# USB_C_Connectors.net
KiCad netlist of a schematic drawn in Altium Designer
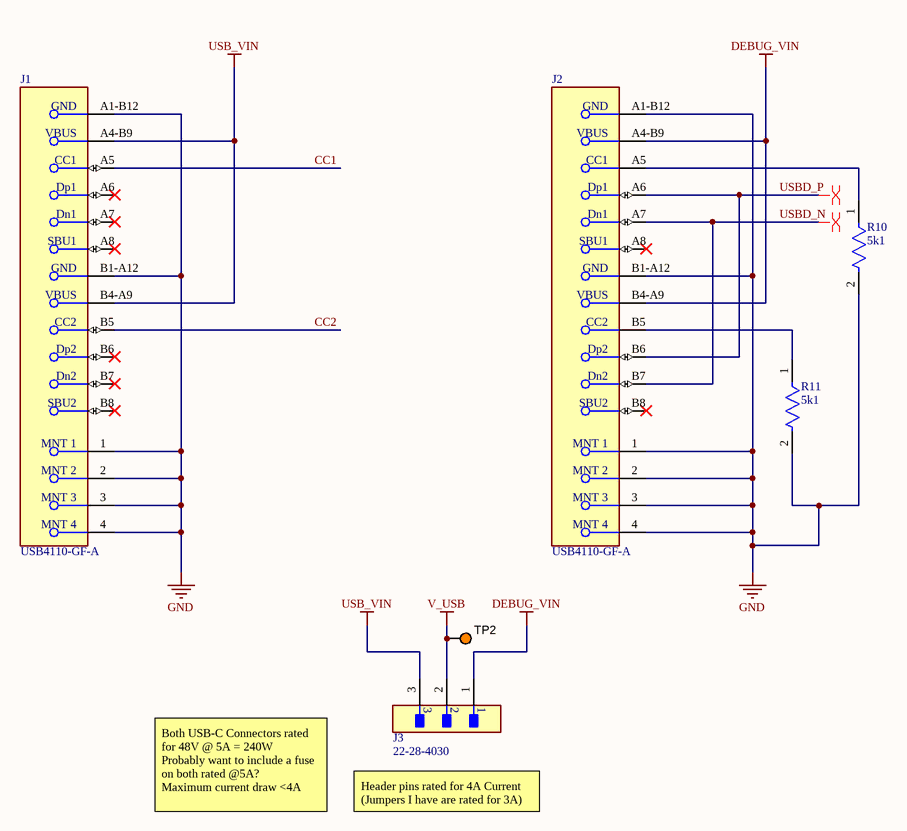
[diagram p0: USB_C_Connectors.SchDoc]

(export (version "E")
  (design (tool "Eeschema 10.0.6"))
  (components
    (comp (ref "J1")
      (value "USB4110-GF-A")
      (footprint "FP-USB4110-GF-A-MFG")
      (description "CONN USB 2.0 TYPE-C R/A SMT")
      (fields
        (field (name "OCTOPART") "https://octopart.com/usb4110-gf-a-gct-103941985")
        (field (name "MANUFACTURER") "GCT")
      )
      (libsource (lib "Altium Content Vault") (part "e23f2b38bb3c3f98e683ebab9ede730"))
    )
    (comp (ref "J2")
      (value "USB4110-GF-A")
      (footprint "FP-USB4110-GF-A-MFG")
      (description "CONN USB 2.0 TYPE-C R/A SMT")
      (fields
        (field (name "OCTOPART") "https://octopart.com/usb4110-gf-a-gct-103941985")
        (field (name "MANUFACTURER") "GCT")
      )
      (libsource (lib "Altium Content Vault") (part "e23f2b38bb3c3f98e683ebab9ede730"))
    )
    (comp (ref "J3")
      (value "22-28-4030")
      (footprint "FP-22-28-4030-MFG")
      (description "CONN HEADER VERT 3POS 2.54MM")
      (fields
        (field (name "OCTOPART") "https://octopart.com/0022284030-molex-10476094")
        (field (name "MANUFACTURER") "Molex")
      )
      (libsource (lib "Altium Content Vault") (part "0d3f023dd272f625e17a2be33dea85f"))
    )
    (comp (ref "R10")
      (value "5k1")
      (footprint "FP-CRCW0603-C-MFG")
      (description "RES 5.1K OHM 5% 1/10W 0603")
      (fields (field (name "TOLERANCE") "5%"))
      (libsource (lib "Altium Content Vault") (part "1029c3af85768c4190bb7ad29bc67b5"))
    )
    (comp (ref "R11")
      (value "5k1")
      (footprint "FP-CRCW0603-C-MFG")
      (description "RES 5.1K OHM 5% 1/10W 0603")
      (fields (field (name "TOLERANCE") "5%"))
      (libsource (lib "Altium Content Vault") (part "1029c3af85768c4190bb7ad29bc67b5"))
    )
    (comp (ref "TP2")
      (value "5003")
      (footprint "KSTN-5003")
      (description "Test Point, Orange, 1-Pin THD, RoHS")
      (libsource (lib "Altium Content Vault") (part "TESTPOINT_ORANGE"))
    )
  )
  (nets
    (net (code "1") (name "/CC1") (class "Default")
      (node (ref "J1") (pin "A5") (pinfunction "CC1_A5") (pintype "bidirectional"))
    )
    (net (code "2") (name "/CC2") (class "Default")
      (node (ref "J1") (pin "B5") (pinfunction "CC2_B5") (pintype "bidirectional"))
    )
    (net (code "3") (name "/USBD_N") (class "Default")
      (node (ref "J2") (pin "A7") (pinfunction "Dn1_A7") (pintype "bidirectional"))
      (node (ref "J2") (pin "B7") (pinfunction "Dn2_B7") (pintype "bidirectional"))
    )
    (net (code "4") (name "/USBD_P") (class "Default")
      (node (ref "J2") (pin "A6") (pinfunction "Dp1_A6") (pintype "bidirectional"))
      (node (ref "J2") (pin "B6") (pinfunction "Dp2_B6") (pintype "bidirectional"))
    )
    (net (code "5") (name "DEBUG_VIN") (class "Default")
      (node (ref "J2") (pin "A4-B9") (pinfunction "VBUS_A4-B9") (pintype "power_in"))
      (node (ref "J2") (pin "B4-A9") (pinfunction "VBUS_B4-A9") (pintype "power_in"))
      (node (ref "J3") (pin "1") (pinfunction "1_1") (pintype "passive"))
    )
    (net (code "6") (name "GND") (class "Default")
      (node (ref "J1") (pin "1") (pinfunction "MNT_1_1") (pintype "passive"))
      (node (ref "J1") (pin "2") (pinfunction "MNT_2_2") (pintype "passive"))
      (node (ref "J1") (pin "3") (pinfunction "MNT_3_3") (pintype "passive"))
      (node (ref "J1") (pin "4") (pinfunction "MNT_4_4") (pintype "passive"))
      (node (ref "J1") (pin "A1-B12") (pinfunction "GND_A1-B12") (pintype "passive"))
      (node (ref "J1") (pin "B1-A12") (pinfunction "GND_B1-A12") (pintype "passive"))
      (node (ref "J2") (pin "1") (pinfunction "MNT_1_1") (pintype "passive"))
      (node (ref "J2") (pin "2") (pinfunction "MNT_2_2") (pintype "passive"))
      (node (ref "J2") (pin "3") (pinfunction "MNT_3_3") (pintype "passive"))
      (node (ref "J2") (pin "4") (pinfunction "MNT_4_4") (pintype "passive"))
      (node (ref "J2") (pin "A1-B12") (pinfunction "GND_A1-B12") (pintype "passive"))
      (node (ref "J2") (pin "B1-A12") (pinfunction "GND_B1-A12") (pintype "passive"))
      (node (ref "R10") (pin "2") (pinfunction "2_2") (pintype "passive"))
      (node (ref "R11") (pin "2") (pinfunction "2_2") (pintype "passive"))
    )
    (net (code "7") (name "Net-(J2-CC1)") (class "Default")
      (node (ref "J2") (pin "A5") (pinfunction "CC1_A5") (pintype "bidirectional"))
      (node (ref "R10") (pin "1") (pinfunction "1_1") (pintype "passive"))
    )
    (net (code "8") (name "Net-(J2-CC2)") (class "Default")
      (node (ref "J2") (pin "B5") (pinfunction "CC2_B5") (pintype "bidirectional"))
      (node (ref "R11") (pin "1") (pinfunction "1_1") (pintype "passive"))
    )
    (net (code "9") (name "USB_VIN") (class "Default")
      (node (ref "J1") (pin "A4-B9") (pinfunction "VBUS_A4-B9") (pintype "power_in"))
      (node (ref "J1") (pin "B4-A9") (pinfunction "VBUS_B4-A9") (pintype "power_in"))
      (node (ref "J3") (pin "3") (pinfunction "3_3") (pintype "passive"))
    )
    (net (code "10") (name "V_USB") (class "Default")
      (node (ref "J3") (pin "2") (pinfunction "2_2") (pintype "passive"))
      (node (ref "TP2") (pin "1") (pinfunction "1_1") (pintype "passive"))
    )
    (net (code "11") (name "unconnected-(J1-Dn1-PadA7)") (class "Default")
      (node (ref "J1") (pin "A7") (pinfunction "Dn1_A7") (pintype "bidirectional+no_connect"))
    )
    (net (code "12") (name "unconnected-(J1-Dn2-PadB7)") (class "Default")
      (node (ref "J1") (pin "B7") (pinfunction "Dn2_B7") (pintype "bidirectional+no_connect"))
    )
    (net (code "13") (name "unconnected-(J1-Dp1-PadA6)") (class "Default")
      (node (ref "J1") (pin "A6") (pinfunction "Dp1_A6") (pintype "bidirectional+no_connect"))
    )
    (net (code "14") (name "unconnected-(J1-Dp2-PadB6)") (class "Default")
      (node (ref "J1") (pin "B6") (pinfunction "Dp2_B6") (pintype "bidirectional+no_connect"))
    )
    (net (code "15") (name "unconnected-(J1-SBU1-PadA8)") (class "Default")
      (node (ref "J1") (pin "A8") (pinfunction "SBU1_A8") (pintype "bidirectional+no_connect"))
    )
    (net (code "16") (name "unconnected-(J1-SBU2-PadB8)") (class "Default")
      (node (ref "J1") (pin "B8") (pinfunction "SBU2_B8") (pintype "bidirectional+no_connect"))
    )
    (net (code "17") (name "unconnected-(J2-SBU1-PadA8)") (class "Default")
      (node (ref "J2") (pin "A8") (pinfunction "SBU1_A8") (pintype "bidirectional+no_connect"))
    )
    (net (code "18") (name "unconnected-(J2-SBU2-PadB8)") (class "Default")
      (node (ref "J2") (pin "B8") (pinfunction "SBU2_B8") (pintype "bidirectional+no_connect"))
    )
  )
)
